# ZP.net
KiCad netlist of a schematic drawn in Altium Designer
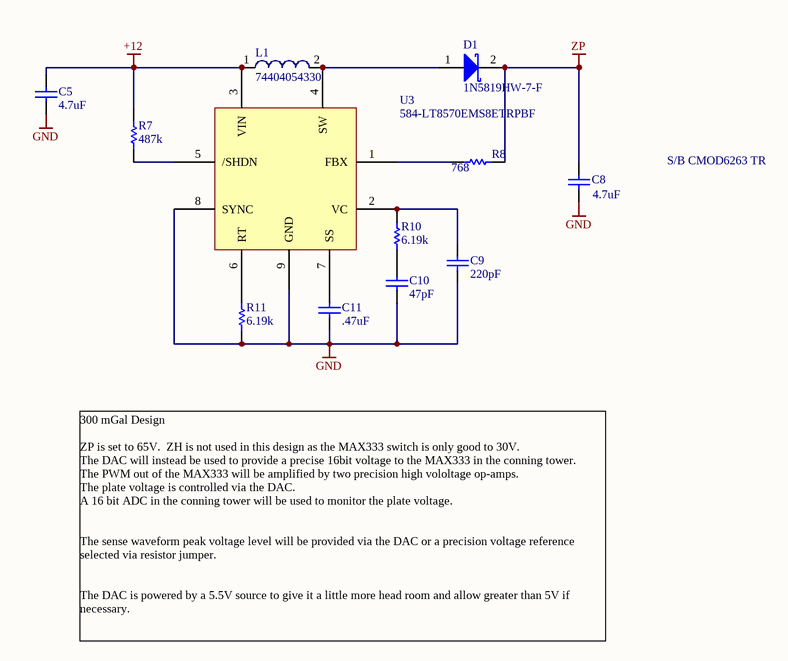
[diagram p0: ZP.SchDoc]

(export (version "E")
  (design (tool "Eeschema 10.0.6"))
  (components
    (comp (ref "C5")
      (value "4.7uF")
      (footprint "CAPC0805(2012)155_L")
      (libsource (lib "Altium Content Vault") (part "CMP-1036-04882-1"))
    )
    (comp (ref "C8")
      (value "CAP CER 1UF 25V X7R 0805")
      (footprint "CAPC0805(2012)155_L")
      (fields
        (field (name "MANUFACTURER") "Murata Electronics North America")
        (field (name "MANUFACTURER PART NUMBER") "GRM21BR71E105KA99L")
        (field (name "CAPACITANCE") "4.7uF")
        (field (name "TOLERANCE") "±10%")
      )
      (libsource (lib "Altium Content Vault") (part "CMP-1036-04882-1"))
    )
    (comp (ref "C9")
      (value "220pF")
      (footprint "CAPC0402(1005)60_L")
      (description "CAP CER 0.1UF 10V X7R 0402")
      (libsource (lib "Altium Content Vault") (part "CMP-1034-00252-1"))
    )
    (comp (ref "C10")
      (value "47pF")
      (footprint "CAPC0402(1005)60_L")
      (description "CAP CER 0.1UF 10V X7R 0402")
      (libsource (lib "Altium Content Vault") (part "CMP-1034-00252-1"))
    )
    (comp (ref "C11")
      (value ".47uF")
      (footprint "CAPC0402(1005)60_L")
      (description "CAP CER 0.1UF 10V X7R 0402")
      (libsource (lib "Altium Content Vault") (part "CMP-1034-00252-1"))
    )
    (comp (ref "D1")
      (value "1N5819HW-7-F")
      (footprint "DIOD-SOD-123-2_V")
      (fields (field (name "MANUFACTURER") "Diodes Inc"))
      (libsource (lib "Altium Content Vault") (part "DIOD-DSKY-A1K2-2"))
    )
    (comp (ref "L1")
      (value "74404054330")
      (footprint "WE-LQS 5040")
      (description "WE-LQS SMD Power Inductor, L=33.0 µH")
      (fields (field (name "MANUFACTURER") "Wuerth Elektronik"))
      (libsource (lib "Altium Content Vault") (part "WE-IND-INDUCTOR-2"))
    )
    (comp (ref "R7")
      (value "487k")
      (footprint "RESC0402(1005)_M")
      (libsource (lib "Altium Content Vault") (part "CMP-1011-00463-1"))
    )
    (comp (ref "R8")
      (value "768")
      (footprint "RESC0402(1005)_M")
      (libsource (lib "Altium Content Vault") (part "CMP-1011-00463-1"))
    )
    (comp (ref "R10")
      (value "6.19k")
      (footprint "RESC0402(1005)_M")
      (libsource (lib "Altium Content Vault") (part "CMP-1011-00463-1"))
    )
    (comp (ref "R11")
      (value "6.19k")
      (footprint "RESC0402(1005)_M")
      (libsource (lib "Altium Content Vault") (part "CMP-1011-00463-1"))
    )
    (comp (ref "U3")
      (value "LT8570")
      (footprint "LT8570-MSOP")
      (description "IC REG MULT CONFIG INV ADJ 8MSOP")
      (fields (field (name "SUPPLIER PART NUMBER 1") "584-LT8570EMS8ETRPBF"))
      (libsource (lib "ZLS_Schematic_lib") (part "LT8570"))
    )
  )
  (nets
    (net (code "1") (name "+12") (class "Default")
      (node (ref "C5") (pin "2") (pinfunction "2_2") (pintype "passive"))
      (node (ref "L1") (pin "1") (pinfunction "1_1") (pintype "passive"))
      (node (ref "R7") (pin "1") (pinfunction "1_1") (pintype "passive"))
      (node (ref "U3") (pin "3") (pinfunction "VIN_3") (pintype "passive"))
    )
    (net (code "2") (name "GND") (class "Default")
      (node (ref "C10") (pin "1") (pinfunction "1_1") (pintype "passive"))
      (node (ref "C11") (pin "1") (pinfunction "1_1") (pintype "passive"))
      (node (ref "C5") (pin "1") (pinfunction "1_1") (pintype "passive"))
      (node (ref "C8") (pin "1") (pinfunction "1_1") (pintype "passive"))
      (node (ref "C9") (pin "1") (pinfunction "1_1") (pintype "passive"))
      (node (ref "R11") (pin "2") (pinfunction "2_2") (pintype "passive"))
      (node (ref "U3") (pin "8") (pinfunction "SYNC_8") (pintype "passive"))
      (node (ref "U3") (pin "9") (pinfunction "GND_9") (pintype "passive"))
    )
    (net (code "3") (name "Net-(C10-Pad2)") (class "Default")
      (node (ref "C10") (pin "2") (pinfunction "2_2") (pintype "passive"))
      (node (ref "R10") (pin "2") (pinfunction "2_2") (pintype "passive"))
    )
    (net (code "4") (name "Net-(D1-A)") (class "Default")
      (node (ref "D1") (pin "1") (pinfunction "A_1") (pintype "passive"))
      (node (ref "L1") (pin "2") (pinfunction "2_2") (pintype "passive"))
      (node (ref "U3") (pin "4") (pinfunction "SW_4") (pintype "passive"))
    )
    (net (code "5") (name "Net-(U3-FBX)") (class "Default")
      (node (ref "R8") (pin "1") (pinfunction "1_1") (pintype "passive"))
      (node (ref "U3") (pin "1") (pinfunction "FBX_1") (pintype "passive"))
    )
    (net (code "6") (name "Net-(U3-RT)") (class "Default")
      (node (ref "R11") (pin "1") (pinfunction "1_1") (pintype "passive"))
      (node (ref "U3") (pin "6") (pinfunction "RT_6") (pintype "passive"))
    )
    (net (code "7") (name "Net-(U3-SS)") (class "Default")
      (node (ref "C11") (pin "2") (pinfunction "2_2") (pintype "passive"))
      (node (ref "U3") (pin "7") (pinfunction "SS_7") (pintype "passive"))
    )
    (net (code "8") (name "Net-(U3-VC)") (class "Default")
      (node (ref "C9") (pin "2") (pinfunction "2_2") (pintype "passive"))
      (node (ref "R10") (pin "1") (pinfunction "1_1") (pintype "passive"))
      (node (ref "U3") (pin "2") (pinfunction "VC_2") (pintype "passive"))
    )
    (net (code "9") (name "Net-(U3-{slash}SHDN)") (class "Default")
      (node (ref "R7") (pin "2") (pinfunction "2_2") (pintype "passive"))
      (node (ref "U3") (pin "5") (pinfunction "/SHDN_5") (pintype "passive"))
    )
    (net (code "10") (name "ZP") (class "Default")
      (node (ref "C8") (pin "2") (pinfunction "2_2") (pintype "passive"))
      (node (ref "D1") (pin "2") (pinfunction "K_2") (pintype "passive"))
      (node (ref "R8") (pin "2") (pinfunction "2_2") (pintype "passive"))
    )
  )
)
